# Muller-C1_2.net
KiCad netlist of a schematic drawn in Altium Designer
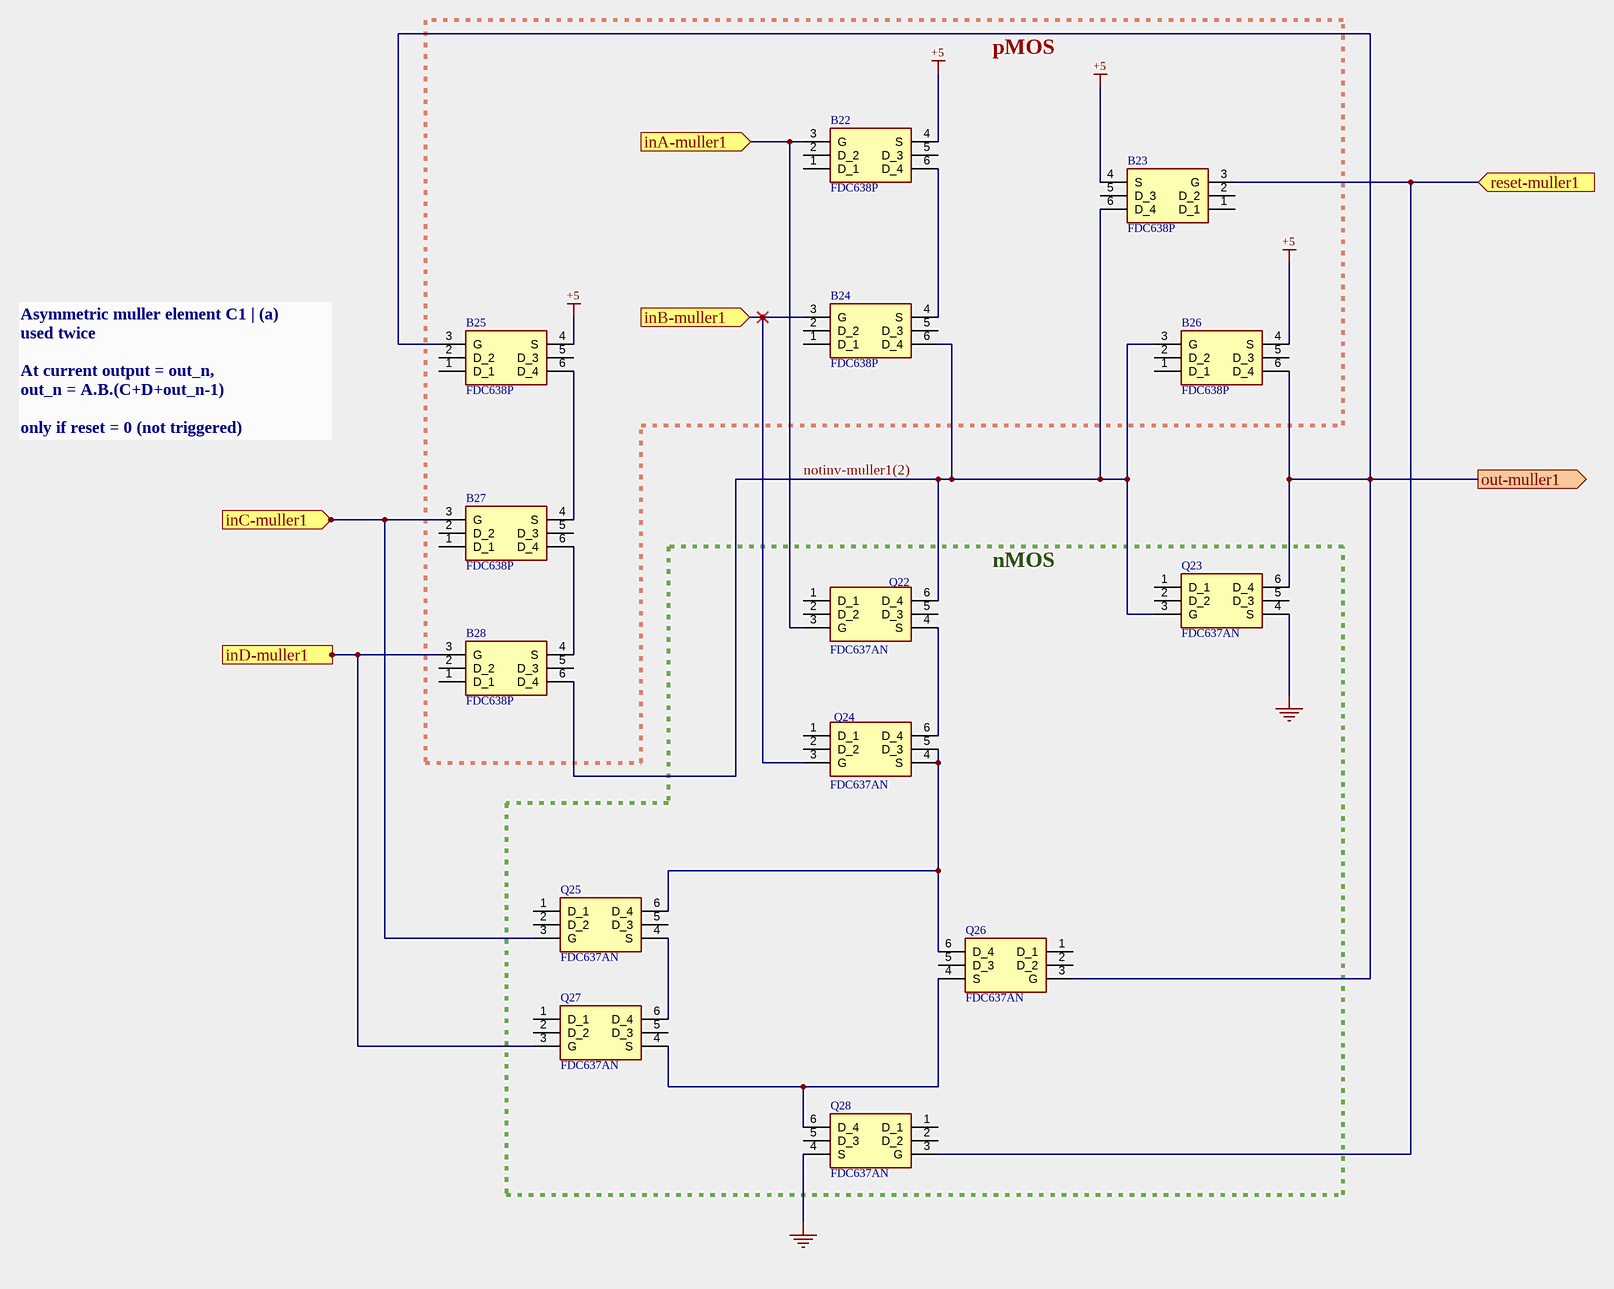
[diagram p0: Muller-C1(2).SchDoc]

(export (version "E")
  (design (tool "Eeschema 10.0.6"))
  (components
    (comp (ref "B22")
      (value "FDC638P")
      (footprint "SOT95P275X110-6N")
      (description "Low gate charge (10 nC typical)")
      (fields (field (name "MOUSER PART NUMBER") "512-FDC638P"))
      (libsource (lib "") (part "FDC638P_1"))
    )
    (comp (ref "B23")
      (value "FDC638P")
      (footprint "SOT95P275X110-6N")
      (description "Low gate charge (10 nC typical)")
      (fields (field (name "MOUSER PART NUMBER") "512-FDC638P"))
      (libsource (lib "iloke") (part "FDC638P"))
    )
    (comp (ref "B24")
      (value "FDC638P")
      (footprint "SOT95P275X110-6N")
      (description "Low gate charge (10 nC typical)")
      (fields (field (name "MOUSER PART NUMBER") "512-FDC638P"))
      (libsource (lib "") (part "FDC638P_1"))
    )
    (comp (ref "B25")
      (value "FDC638P")
      (footprint "SOT95P275X110-6N")
      (description "Low gate charge (10 nC typical)")
      (fields (field (name "MOUSER PART NUMBER") "512-FDC638P"))
      (libsource (lib "") (part "FDC638P_1"))
    )
    (comp (ref "B26")
      (value "FDC638P")
      (footprint "SOT95P275X110-6N")
      (description "Low gate charge (10 nC typical)")
      (fields (field (name "MOUSER PART NUMBER") "512-FDC638P"))
      (libsource (lib "") (part "FDC638P_1"))
    )
    (comp (ref "B27")
      (value "FDC638P")
      (footprint "SOT95P275X110-6N")
      (description "Low gate charge (10 nC typical)")
      (fields (field (name "MOUSER PART NUMBER") "512-FDC638P"))
      (libsource (lib "") (part "FDC638P_1"))
    )
    (comp (ref "B28")
      (value "FDC638P")
      (footprint "SOT95P275X110-6N")
      (description "Low gate charge (10 nC typical)")
      (fields (field (name "MOUSER PART NUMBER") "512-FDC638P"))
      (libsource (lib "") (part "FDC638P_1"))
    )
    (comp (ref "Q22")
      (value "FDC637AN")
      (footprint "SOT95P275X110-6N")
      (description "Low gate charge (10.5nC typical).")
      (fields (field (name "MOUSER PART NUMBER") "512-FDC637AN"))
      (libsource (lib "iloke") (part "FDC637AN"))
    )
    (comp (ref "Q23")
      (value "FDC637AN")
      (footprint "SOT95P275X110-6N")
      (description "Low gate charge (10.5nC typical).")
      (fields (field (name "MOUSER PART NUMBER") "512-FDC637AN"))
      (libsource (lib "iloke") (part "FDC637AN"))
    )
    (comp (ref "Q24")
      (value "FDC637AN")
      (footprint "SOT95P275X110-6N")
      (description "Low gate charge (10.5nC typical).")
      (fields (field (name "MOUSER PART NUMBER") "512-FDC637AN"))
      (libsource (lib "iloke") (part "FDC637AN"))
    )
    (comp (ref "Q25")
      (value "FDC637AN")
      (footprint "SOT95P275X110-6N")
      (description "Low gate charge (10.5nC typical).")
      (fields (field (name "MOUSER PART NUMBER") "512-FDC637AN"))
      (libsource (lib "iloke") (part "FDC637AN"))
    )
    (comp (ref "Q26")
      (value "FDC637AN")
      (footprint "SOT95P275X110-6N")
      (description "Low gate charge (10.5nC typical).")
      (fields (field (name "MOUSER PART NUMBER") "512-FDC637AN"))
      (libsource (lib "") (part "FDC637AN_1"))
    )
    (comp (ref "Q27")
      (value "FDC637AN")
      (footprint "SOT95P275X110-6N")
      (description "Low gate charge (10.5nC typical).")
      (fields (field (name "MOUSER PART NUMBER") "512-FDC637AN"))
      (libsource (lib "iloke") (part "FDC637AN"))
    )
    (comp (ref "Q28")
      (value "FDC637AN")
      (footprint "SOT95P275X110-6N")
      (description "Low gate charge (10.5nC typical).")
      (fields (field (name "MOUSER PART NUMBER") "512-FDC637AN"))
      (libsource (lib "") (part "FDC637AN_1"))
    )
  )
  (nets
    (net (code "1") (name "+5") (class "Default")
      (node (ref "B22") (pin "4") (pinfunction "S_4") (pintype "passive"))
      (node (ref "B23") (pin "4") (pinfunction "S_4") (pintype "passive"))
      (node (ref "B25") (pin "4") (pinfunction "S_4") (pintype "passive"))
      (node (ref "B26") (pin "4") (pinfunction "S_4") (pintype "passive"))
    )
    (net (code "2") (name "/inA-muller1") (class "Default")
      (node (ref "B22") (pin "3") (pinfunction "G_3") (pintype "passive"))
      (node (ref "Q22") (pin "3") (pinfunction "G_3") (pintype "passive"))
    )
    (net (code "3") (name "/inB-muller1") (class "Default")
      (node (ref "B24") (pin "3") (pinfunction "G_3") (pintype "passive"))
      (node (ref "Q24") (pin "3") (pinfunction "G_3") (pintype "passive"))
    )
    (net (code "4") (name "/inC-muller1") (class "Default")
      (node (ref "B27") (pin "3") (pinfunction "G_3") (pintype "passive"))
      (node (ref "Q25") (pin "3") (pinfunction "G_3") (pintype "passive"))
    )
    (net (code "5") (name "/inD-muller1") (class "Default")
      (node (ref "B28") (pin "3") (pinfunction "G_3") (pintype "passive"))
      (node (ref "Q27") (pin "3") (pinfunction "G_3") (pintype "passive"))
    )
    (net (code "6") (name "/notinv-muller1(2)") (class "Default")
      (node (ref "B23") (pin "6") (pinfunction "D_4_6") (pintype "passive"))
      (node (ref "B24") (pin "6") (pinfunction "D_4_6") (pintype "passive"))
      (node (ref "B26") (pin "3") (pinfunction "G_3") (pintype "passive"))
      (node (ref "B28") (pin "6") (pinfunction "D_4_6") (pintype "passive"))
      (node (ref "Q22") (pin "6") (pinfunction "D_4_6") (pintype "passive"))
      (node (ref "Q23") (pin "3") (pinfunction "G_3") (pintype "passive"))
    )
    (net (code "7") (name "/out-muller1") (class "Default")
      (node (ref "B25") (pin "3") (pinfunction "G_3") (pintype "passive"))
      (node (ref "B26") (pin "6") (pinfunction "D_4_6") (pintype "passive"))
      (node (ref "Q23") (pin "6") (pinfunction "D_4_6") (pintype "passive"))
      (node (ref "Q26") (pin "3") (pinfunction "G_3") (pintype "passive"))
    )
    (net (code "8") (name "/reset-muller1") (class "Default")
      (node (ref "B23") (pin "3") (pinfunction "G_3") (pintype "passive"))
      (node (ref "Q28") (pin "3") (pinfunction "G_3") (pintype "passive"))
    )
    (net (code "9") (name "GND") (class "Default")
      (node (ref "Q23") (pin "4") (pinfunction "S_4") (pintype "passive"))
      (node (ref "Q28") (pin "4") (pinfunction "S_4") (pintype "passive"))
    )
    (net (code "10") (name "Net-(B22-D_4)") (class "Default")
      (node (ref "B22") (pin "6") (pinfunction "D_4_6") (pintype "passive"))
      (node (ref "B24") (pin "4") (pinfunction "S_4") (pintype "passive"))
    )
    (net (code "11") (name "Net-(B25-D_4)") (class "Default")
      (node (ref "B25") (pin "6") (pinfunction "D_4_6") (pintype "passive"))
      (node (ref "B27") (pin "4") (pinfunction "S_4") (pintype "passive"))
    )
    (net (code "12") (name "Net-(B27-D_4)") (class "Default")
      (node (ref "B27") (pin "6") (pinfunction "D_4_6") (pintype "passive"))
      (node (ref "B28") (pin "4") (pinfunction "S_4") (pintype "passive"))
    )
    (net (code "13") (name "Net-(Q22-S)") (class "Default")
      (node (ref "Q22") (pin "4") (pinfunction "S_4") (pintype "passive"))
      (node (ref "Q24") (pin "6") (pinfunction "D_4_6") (pintype "passive"))
    )
    (net (code "14") (name "Net-(Q24-D_3)") (class "Default")
      (node (ref "Q24") (pin "4") (pinfunction "S_4") (pintype "passive"))
      (node (ref "Q24") (pin "5") (pinfunction "D_3_5") (pintype "passive"))
      (node (ref "Q25") (pin "6") (pinfunction "D_4_6") (pintype "passive"))
      (node (ref "Q26") (pin "6") (pinfunction "D_4_6") (pintype "passive"))
    )
    (net (code "15") (name "Net-(Q25-S)") (class "Default")
      (node (ref "Q25") (pin "4") (pinfunction "S_4") (pintype "passive"))
      (node (ref "Q27") (pin "6") (pinfunction "D_4_6") (pintype "passive"))
    )
    (net (code "16") (name "Net-(Q26-S)") (class "Default")
      (node (ref "Q26") (pin "4") (pinfunction "S_4") (pintype "passive"))
      (node (ref "Q27") (pin "4") (pinfunction "S_4") (pintype "passive"))
      (node (ref "Q28") (pin "6") (pinfunction "D_4_6") (pintype "passive"))
    )
    (net (code "17") (name "unconnected-(B22-D_1-Pad1)") (class "Default")
      (node (ref "B22") (pin "1") (pinfunction "D_1_1") (pintype "passive"))
    )
    (net (code "18") (name "unconnected-(B22-D_2-Pad2)") (class "Default")
      (node (ref "B22") (pin "2") (pinfunction "D_2_2") (pintype "passive"))
    )
    (net (code "19") (name "unconnected-(B22-D_3-Pad5)") (class "Default")
      (node (ref "B22") (pin "5") (pinfunction "D_3_5") (pintype "passive"))
    )
    (net (code "20") (name "unconnected-(B23-D_1-Pad1)") (class "Default")
      (node (ref "B23") (pin "1") (pinfunction "D_1_1") (pintype "passive"))
    )
    (net (code "21") (name "unconnected-(B23-D_2-Pad2)") (class "Default")
      (node (ref "B23") (pin "2") (pinfunction "D_2_2") (pintype "passive"))
    )
    (net (code "22") (name "unconnected-(B23-D_3-Pad5)") (class "Default")
      (node (ref "B23") (pin "5") (pinfunction "D_3_5") (pintype "passive"))
    )
    (net (code "23") (name "unconnected-(B24-D_1-Pad1)") (class "Default")
      (node (ref "B24") (pin "1") (pinfunction "D_1_1") (pintype "passive"))
    )
    (net (code "24") (name "unconnected-(B24-D_2-Pad2)") (class "Default")
      (node (ref "B24") (pin "2") (pinfunction "D_2_2") (pintype "passive"))
    )
    (net (code "25") (name "unconnected-(B24-D_3-Pad5)") (class "Default")
      (node (ref "B24") (pin "5") (pinfunction "D_3_5") (pintype "passive"))
    )
    (net (code "26") (name "unconnected-(B25-D_1-Pad1)") (class "Default")
      (node (ref "B25") (pin "1") (pinfunction "D_1_1") (pintype "passive"))
    )
    (net (code "27") (name "unconnected-(B25-D_2-Pad2)") (class "Default")
      (node (ref "B25") (pin "2") (pinfunction "D_2_2") (pintype "passive"))
    )
    (net (code "28") (name "unconnected-(B25-D_3-Pad5)") (class "Default")
      (node (ref "B25") (pin "5") (pinfunction "D_3_5") (pintype "passive"))
    )
    (net (code "29") (name "unconnected-(B26-D_1-Pad1)") (class "Default")
      (node (ref "B26") (pin "1") (pinfunction "D_1_1") (pintype "passive"))
    )
    (net (code "30") (name "unconnected-(B26-D_2-Pad2)") (class "Default")
      (node (ref "B26") (pin "2") (pinfunction "D_2_2") (pintype "passive"))
    )
    (net (code "31") (name "unconnected-(B26-D_3-Pad5)") (class "Default")
      (node (ref "B26") (pin "5") (pinfunction "D_3_5") (pintype "passive"))
    )
    (net (code "32") (name "unconnected-(B27-D_1-Pad1)") (class "Default")
      (node (ref "B27") (pin "1") (pinfunction "D_1_1") (pintype "passive"))
    )
    (net (code "33") (name "unconnected-(B27-D_2-Pad2)") (class "Default")
      (node (ref "B27") (pin "2") (pinfunction "D_2_2") (pintype "passive"))
    )
    (net (code "34") (name "unconnected-(B27-D_3-Pad5)") (class "Default")
      (node (ref "B27") (pin "5") (pinfunction "D_3_5") (pintype "passive"))
    )
    (net (code "35") (name "unconnected-(B28-D_1-Pad1)") (class "Default")
      (node (ref "B28") (pin "1") (pinfunction "D_1_1") (pintype "passive"))
    )
    (net (code "36") (name "unconnected-(B28-D_2-Pad2)") (class "Default")
      (node (ref "B28") (pin "2") (pinfunction "D_2_2") (pintype "passive"))
    )
    (net (code "37") (name "unconnected-(B28-D_3-Pad5)") (class "Default")
      (node (ref "B28") (pin "5") (pinfunction "D_3_5") (pintype "passive"))
    )
    (net (code "38") (name "unconnected-(Q22-D_1-Pad1)") (class "Default")
      (node (ref "Q22") (pin "1") (pinfunction "D_1_1") (pintype "passive"))
    )
    (net (code "39") (name "unconnected-(Q22-D_2-Pad2)") (class "Default")
      (node (ref "Q22") (pin "2") (pinfunction "D_2_2") (pintype "passive"))
    )
    (net (code "40") (name "unconnected-(Q22-D_3-Pad5)") (class "Default")
      (node (ref "Q22") (pin "5") (pinfunction "D_3_5") (pintype "passive"))
    )
    (net (code "41") (name "unconnected-(Q23-D_1-Pad1)") (class "Default")
      (node (ref "Q23") (pin "1") (pinfunction "D_1_1") (pintype "passive"))
    )
    (net (code "42") (name "unconnected-(Q23-D_2-Pad2)") (class "Default")
      (node (ref "Q23") (pin "2") (pinfunction "D_2_2") (pintype "passive"))
    )
    (net (code "43") (name "unconnected-(Q23-D_3-Pad5)") (class "Default")
      (node (ref "Q23") (pin "5") (pinfunction "D_3_5") (pintype "passive"))
    )
    (net (code "44") (name "unconnected-(Q24-D_1-Pad1)") (class "Default")
      (node (ref "Q24") (pin "1") (pinfunction "D_1_1") (pintype "passive"))
    )
    (net (code "45") (name "unconnected-(Q24-D_2-Pad2)") (class "Default")
      (node (ref "Q24") (pin "2") (pinfunction "D_2_2") (pintype "passive"))
    )
    (net (code "46") (name "unconnected-(Q25-D_1-Pad1)") (class "Default")
      (node (ref "Q25") (pin "1") (pinfunction "D_1_1") (pintype "passive"))
    )
    (net (code "47") (name "unconnected-(Q25-D_2-Pad2)") (class "Default")
      (node (ref "Q25") (pin "2") (pinfunction "D_2_2") (pintype "passive"))
    )
    (net (code "48") (name "unconnected-(Q25-D_3-Pad5)") (class "Default")
      (node (ref "Q25") (pin "5") (pinfunction "D_3_5") (pintype "passive"))
    )
    (net (code "49") (name "unconnected-(Q26-D_1-Pad1)") (class "Default")
      (node (ref "Q26") (pin "1") (pinfunction "D_1_1") (pintype "passive"))
    )
    (net (code "50") (name "unconnected-(Q26-D_2-Pad2)") (class "Default")
      (node (ref "Q26") (pin "2") (pinfunction "D_2_2") (pintype "passive"))
    )
    (net (code "51") (name "unconnected-(Q26-D_3-Pad5)") (class "Default")
      (node (ref "Q26") (pin "5") (pinfunction "D_3_5") (pintype "passive"))
    )
    (net (code "52") (name "unconnected-(Q27-D_1-Pad1)") (class "Default")
      (node (ref "Q27") (pin "1") (pinfunction "D_1_1") (pintype "passive"))
    )
    (net (code "53") (name "unconnected-(Q27-D_2-Pad2)") (class "Default")
      (node (ref "Q27") (pin "2") (pinfunction "D_2_2") (pintype "passive"))
    )
    (net (code "54") (name "unconnected-(Q27-D_3-Pad5)") (class "Default")
      (node (ref "Q27") (pin "5") (pinfunction "D_3_5") (pintype "passive"))
    )
    (net (code "55") (name "unconnected-(Q28-D_1-Pad1)") (class "Default")
      (node (ref "Q28") (pin "1") (pinfunction "D_1_1") (pintype "passive"))
    )
    (net (code "56") (name "unconnected-(Q28-D_2-Pad2)") (class "Default")
      (node (ref "Q28") (pin "2") (pinfunction "D_2_2") (pintype "passive"))
    )
    (net (code "57") (name "unconnected-(Q28-D_3-Pad5)") (class "Default")
      (node (ref "Q28") (pin "5") (pinfunction "D_3_5") (pintype "passive"))
    )
  )
)
